# GNSS_modulis.net
KiCad netlist of a schematic drawn in Altium Designer
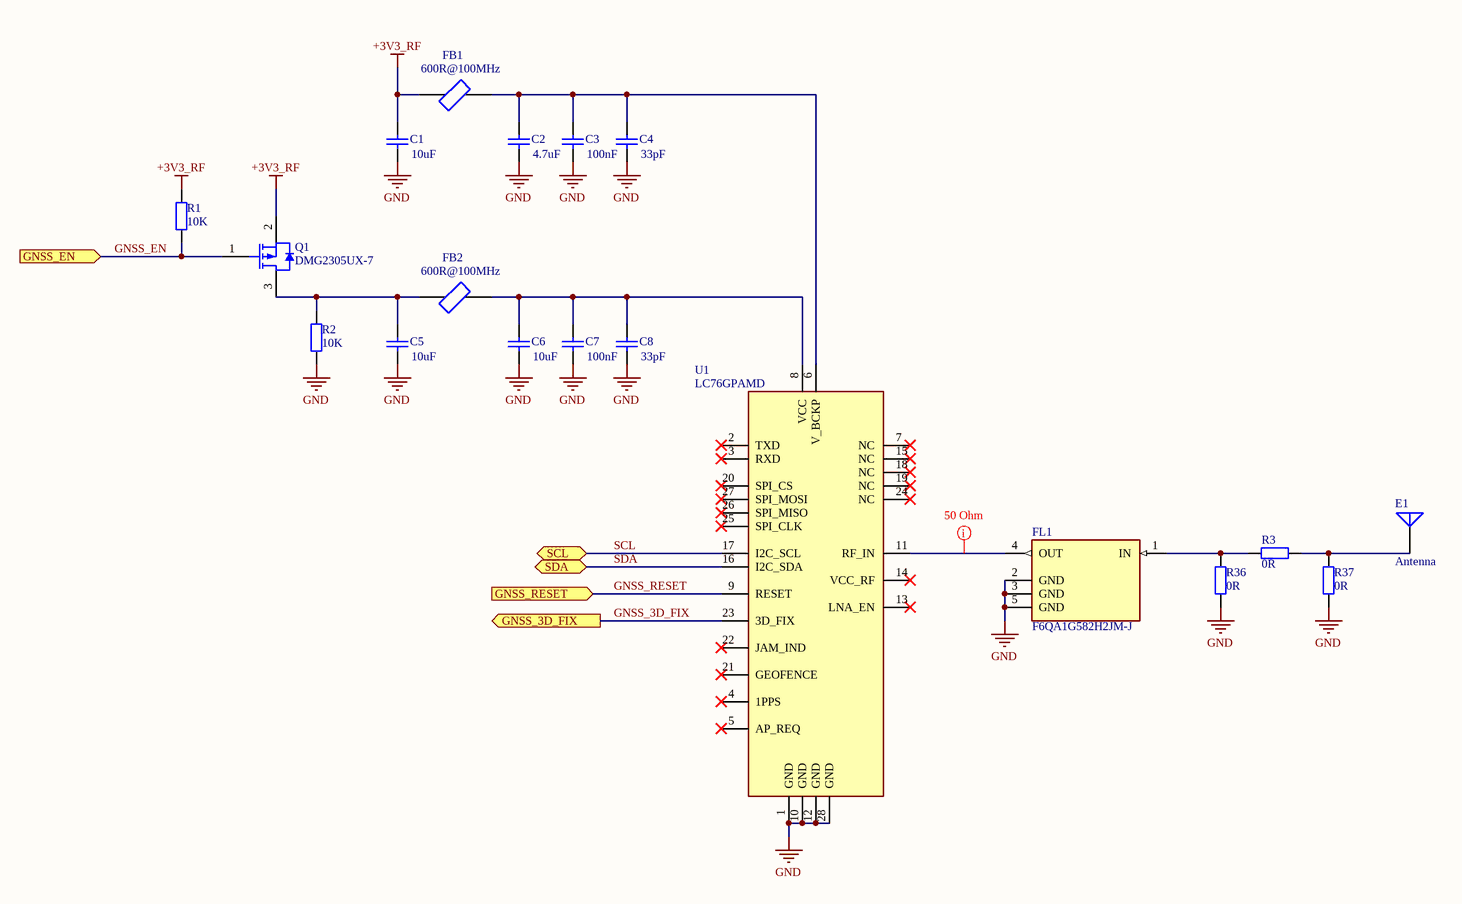
[diagram p0: GNSS modulis.SchDoc]

(export (version "E")
  (design (tool "Eeschema 10.0.6"))
  (components
    (comp (ref "C1")
      (value "10uF")
      (footprint "0402")
      (description "Capacitor")
      (fields (field (name "PUBLISHER") "Altium Limited"))
      (libsource (lib "Miscellaneous Devices") (part "Cap"))
    )
    (comp (ref "C2")
      (value "4.7uF")
      (footprint "0402")
      (description "Capacitor")
      (fields (field (name "PUBLISHER") "Altium Limited"))
      (libsource (lib "Miscellaneous Devices") (part "Cap"))
    )
    (comp (ref "C3")
      (value "100nF")
      (footprint "0402")
      (description "Capacitor")
      (fields (field (name "PUBLISHER") "Altium Limited"))
      (libsource (lib "Miscellaneous Devices") (part "Cap"))
    )
    (comp (ref "C4")
      (value "33pF")
      (footprint "0402")
      (description "Capacitor")
      (fields (field (name "PUBLISHER") "Altium Limited"))
      (libsource (lib "Miscellaneous Devices") (part "Cap"))
    )
    (comp (ref "C5")
      (value "10uF")
      (footprint "0402")
      (description "Capacitor")
      (fields (field (name "PUBLISHER") "Altium Limited"))
      (libsource (lib "Miscellaneous Devices") (part "Cap"))
    )
    (comp (ref "C6")
      (value "10uF")
      (footprint "0402")
      (description "Capacitor")
      (fields (field (name "PUBLISHER") "Altium Limited"))
      (libsource (lib "Miscellaneous Devices") (part "Cap"))
    )
    (comp (ref "C7")
      (value "100nF")
      (footprint "0402")
      (description "Capacitor")
      (fields (field (name "PUBLISHER") "Altium Limited"))
      (libsource (lib "Miscellaneous Devices") (part "Cap"))
    )
    (comp (ref "C8")
      (value "33pF")
      (footprint "0402")
      (description "Capacitor")
      (fields (field (name "PUBLISHER") "Altium Limited"))
      (libsource (lib "Miscellaneous Devices") (part "Cap"))
    )
    (comp (ref "E1")
      (value "Antenna")
      (footprint "204286-0001_MOL")
      (description "Generic Antenna")
      (fields (field (name "PUBLISHER") "Altium Limited"))
      (libsource (lib "Miscellaneous Devices") (part "Antenna"))
    )
    (comp (ref "FB1")
      (value "600R@100MHz")
      (footprint "0402 Ferrite Bead")
      (description "Ferrite Beads FERRITE BEAD 600 OHM 0603 1LN")
      (fields (field (name "MF") "Laird-Signal Integrity Products") (field (name "MP") "MI0805K400R-10"))
      (libsource (lib "Schematic_library") (part "Ferrite"))
    )
    (comp (ref "FB2")
      (value "600R@100MHz")
      (footprint "0402 Ferrite Bead")
      (description "Ferrite Beads FERRITE BEAD 600 OHM 0603 1LN")
      (fields (field (name "MF") "Laird-Signal Integrity Products") (field (name "MP") "MI0805K400R-10"))
      (libsource (lib "Schematic_library") (part "Ferrite"))
    )
    (comp (ref "FL1")
      (value "F6QA1G582H2JM-J")
      (footprint "FIL_F6QA1G582H2JM-J")
      (description "1.582GHz Frequency GPS RF SAW Filter (Surface Acoustic Wave) 1.8dB  Bandwidth 5-SMD, No Lead")
      (fields (field (name "MF") "Taiyo Yuden"))
      (libsource (lib "Schematic_library") (part "F6QA1G582H2JM-J"))
    )
    (comp (ref "Q1")
      (value "DMG2305UX-7")
      (footprint "JSCJ-SOT23-3_V")
      (description "P-Channel Plastic Encapsulate MOSFET, 12 V, 4.1 A, 3-Pin SOT23, Tape and Reel")
      (fields (field (name "MANUFACTURER") "Jiangsu Changjiang Electronics Technology"))
      (libsource (lib "Ernestas Krikščiūnas") (part "PEMOS-GSD-3"))
    )
    (comp (ref "R1")
      (value "10K")
      (footprint "SMD-0402-RES")
      (description "Resistor")
      (fields (field (name "PUBLISHER") "Altium Limited"))
      (libsource (lib "Miscellaneous Devices") (part "Res2"))
    )
    (comp (ref "R2")
      (value "10K")
      (footprint "SMD-0402-RES")
      (description "Resistor")
      (fields (field (name "PUBLISHER") "Altium Limited"))
      (libsource (lib "Miscellaneous Devices") (part "Res2"))
    )
    (comp (ref "R3")
      (value "0R")
      (footprint "SMD-0402-RES")
      (description "Resistor")
      (fields (field (name "PUBLISHER") "Altium Limited"))
      (libsource (lib "") (part "Res2_1"))
    )
    (comp (ref "R36")
      (value "0R")
      (footprint "SMD-0402-RES")
      (description "Resistor")
      (fields (field (name "PUBLISHER") "Altium Limited"))
      (libsource (lib "Miscellaneous Devices") (part "Res2"))
    )
    (comp (ref "R37")
      (value "0R")
      (footprint "SMD-0402-RES")
      (description "Resistor")
      (fields (field (name "PUBLISHER") "Altium Limited"))
      (libsource (lib "Miscellaneous Devices") (part "Res2"))
    )
    (comp (ref "U1")
      (value "LC76GPAMD")
      (footprint "SamacSys:LC76GPAMD")
      (fields (field (name "MOUSER PART NUMBER") "277-LC76GPAMD"))
      (libsource (lib "Schematic_library") (part "LC76GPAMD"))
    )
  )
  (nets
    (net (code "1") (name "+3V3_RF") (class "Default")
      (node (ref "C1") (pin "2") (pinfunction "2_2") (pintype "passive"))
      (node (ref "FB1") (pin "1") (pinfunction "1_1") (pintype "passive"))
      (node (ref "Q1") (pin "2") (pinfunction "SOURCE_2") (pintype "passive"))
      (node (ref "R1") (pin "2") (pinfunction "2_2") (pintype "passive"))
    )
    (net (code "2") (name "/GNSS_3D_FIX") (class "Default")
      (node (ref "U1") (pin "23") (pinfunction "3D_FIX_23") (pintype "passive"))
    )
    (net (code "3") (name "/GNSS_EN") (class "Default")
      (node (ref "Q1") (pin "1") (pinfunction "GATE_1") (pintype "passive"))
      (node (ref "R1") (pin "1") (pinfunction "1_1") (pintype "passive"))
    )
    (net (code "4") (name "/GNSS_RESET") (class "Default")
      (node (ref "U1") (pin "9") (pinfunction "RESET_9") (pintype "passive"))
    )
    (net (code "5") (name "/SCL") (class "Default")
      (node (ref "U1") (pin "17") (pinfunction "I2C_SCL_17") (pintype "passive"))
    )
    (net (code "6") (name "/SDA") (class "Default")
      (node (ref "U1") (pin "16") (pinfunction "I2C_SDA_16") (pintype "passive"))
    )
    (net (code "7") (name "GND") (class "Default")
      (node (ref "C1") (pin "1") (pinfunction "1_1") (pintype "passive"))
      (node (ref "C2") (pin "1") (pinfunction "1_1") (pintype "passive"))
      (node (ref "C3") (pin "1") (pinfunction "1_1") (pintype "passive"))
      (node (ref "C4") (pin "1") (pinfunction "1_1") (pintype "passive"))
      (node (ref "C5") (pin "1") (pinfunction "1_1") (pintype "passive"))
      (node (ref "C6") (pin "1") (pinfunction "1_1") (pintype "passive"))
      (node (ref "C7") (pin "1") (pinfunction "1_1") (pintype "passive"))
      (node (ref "C8") (pin "1") (pinfunction "1_1") (pintype "passive"))
      (node (ref "FL1") (pin "2") (pinfunction "GND_2") (pintype "power_in"))
      (node (ref "FL1") (pin "3") (pinfunction "GND_3") (pintype "power_in"))
      (node (ref "FL1") (pin "5") (pinfunction "GND_5") (pintype "power_in"))
      (node (ref "R2") (pin "1") (pinfunction "1_1") (pintype "passive"))
      (node (ref "R36") (pin "1") (pinfunction "1_1") (pintype "passive"))
      (node (ref "R37") (pin "1") (pinfunction "1_1") (pintype "passive"))
      (node (ref "U1") (pin "1") (pinfunction "GND_1") (pintype "passive"))
      (node (ref "U1") (pin "10") (pinfunction "GND_10") (pintype "passive"))
      (node (ref "U1") (pin "12") (pinfunction "GND_12") (pintype "passive"))
      (node (ref "U1") (pin "28") (pinfunction "GND_28") (pintype "passive"))
    )
    (net (code "8") (name "Net-(E1-A)") (class "Default")
      (node (ref "E1") (pin "1") (pinfunction "A_1") (pintype "passive"))
      (node (ref "R3") (pin "2") (pinfunction "2_2") (pintype "passive"))
      (node (ref "R37") (pin "2") (pinfunction "2_2") (pintype "passive"))
    )
    (net (code "9") (name "Net-(FL1-IN)") (class "Default")
      (node (ref "FL1") (pin "1") (pinfunction "IN_1") (pintype "input"))
      (node (ref "R3") (pin "1") (pinfunction "1_1") (pintype "passive"))
      (node (ref "R36") (pin "2") (pinfunction "2_2") (pintype "passive"))
    )
    (net (code "10") (name "Net-(FL1-OUT)") (class "Default")
      (node (ref "FL1") (pin "4") (pinfunction "OUT_4") (pintype "output"))
      (node (ref "U1") (pin "11") (pinfunction "RF_IN_11") (pintype "passive"))
    )
    (net (code "11") (name "Net-(Q1-DRAIN)") (class "Default")
      (node (ref "C5") (pin "2") (pinfunction "2_2") (pintype "passive"))
      (node (ref "FB2") (pin "1") (pinfunction "1_1") (pintype "passive"))
      (node (ref "Q1") (pin "3") (pinfunction "DRAIN_3") (pintype "passive"))
      (node (ref "R2") (pin "2") (pinfunction "2_2") (pintype "passive"))
    )
    (net (code "12") (name "Net-(U1-VCC)") (class "Default")
      (node (ref "C6") (pin "2") (pinfunction "2_2") (pintype "passive"))
      (node (ref "C7") (pin "2") (pinfunction "2_2") (pintype "passive"))
      (node (ref "C8") (pin "2") (pinfunction "2_2") (pintype "passive"))
      (node (ref "FB2") (pin "2") (pinfunction "2_2") (pintype "passive"))
      (node (ref "U1") (pin "8") (pinfunction "VCC_8") (pintype "passive"))
    )
    (net (code "13") (name "Net-(U1-V_BCKP)") (class "Default")
      (node (ref "C2") (pin "2") (pinfunction "2_2") (pintype "passive"))
      (node (ref "C3") (pin "2") (pinfunction "2_2") (pintype "passive"))
      (node (ref "C4") (pin "2") (pinfunction "2_2") (pintype "passive"))
      (node (ref "FB1") (pin "2") (pinfunction "2_2") (pintype "passive"))
      (node (ref "U1") (pin "6") (pinfunction "V_BCKP_6") (pintype "passive"))
    )
    (net (code "14") (name "unconnected-(U1-1PPS-Pad4)") (class "Default")
      (node (ref "U1") (pin "4") (pinfunction "1PPS_4") (pintype "passive+no_connect"))
    )
    (net (code "15") (name "unconnected-(U1-AP_REQ-Pad5)") (class "Default")
      (node (ref "U1") (pin "5") (pinfunction "AP_REQ_5") (pintype "passive+no_connect"))
    )
    (net (code "16") (name "unconnected-(U1-GEOFENCE-Pad21)") (class "Default")
      (node (ref "U1") (pin "21") (pinfunction "GEOFENCE_21") (pintype "passive+no_connect"))
    )
    (net (code "17") (name "unconnected-(U1-JAM_IND-Pad22)") (class "Default")
      (node (ref "U1") (pin "22") (pinfunction "JAM_IND_22") (pintype "passive+no_connect"))
    )
    (net (code "18") (name "unconnected-(U1-LNA_EN-Pad13)") (class "Default")
      (node (ref "U1") (pin "13") (pinfunction "LNA_EN_13") (pintype "passive+no_connect"))
    )
    (net (code "19") (name "unconnected-(U1-NC-Pad7)") (class "Default")
      (node (ref "U1") (pin "7") (pinfunction "NC_7") (pintype "passive+no_connect"))
    )
    (net (code "20") (name "unconnected-(U1-NC-Pad15)") (class "Default")
      (node (ref "U1") (pin "15") (pinfunction "NC_15") (pintype "passive+no_connect"))
    )
    (net (code "21") (name "unconnected-(U1-NC-Pad18)") (class "Default")
      (node (ref "U1") (pin "18") (pinfunction "NC_18") (pintype "passive+no_connect"))
    )
    (net (code "22") (name "unconnected-(U1-NC-Pad19)") (class "Default")
      (node (ref "U1") (pin "19") (pinfunction "NC_19") (pintype "passive+no_connect"))
    )
    (net (code "23") (name "unconnected-(U1-NC-Pad24)") (class "Default")
      (node (ref "U1") (pin "24") (pinfunction "NC_24") (pintype "passive+no_connect"))
    )
    (net (code "24") (name "unconnected-(U1-RXD-Pad3)") (class "Default")
      (node (ref "U1") (pin "3") (pinfunction "RXD_3") (pintype "passive+no_connect"))
    )
    (net (code "25") (name "unconnected-(U1-SPI_CLK-Pad25)") (class "Default")
      (node (ref "U1") (pin "25") (pinfunction "SPI_CLK_25") (pintype "passive+no_connect"))
    )
    (net (code "26") (name "unconnected-(U1-SPI_CS-Pad20)") (class "Default")
      (node (ref "U1") (pin "20") (pinfunction "SPI_CS_20") (pintype "passive+no_connect"))
    )
    (net (code "27") (name "unconnected-(U1-SPI_MISO-Pad26)") (class "Default")
      (node (ref "U1") (pin "26") (pinfunction "SPI_MISO_26") (pintype "passive+no_connect"))
    )
    (net (code "28") (name "unconnected-(U1-SPI_MOSI-Pad27)") (class "Default")
      (node (ref "U1") (pin "27") (pinfunction "SPI_MOSI_27") (pintype "passive+no_connect"))
    )
    (net (code "29") (name "unconnected-(U1-TXD-Pad2)") (class "Default")
      (node (ref "U1") (pin "2") (pinfunction "TXD_2") (pintype "passive+no_connect"))
    )
    (net (code "30") (name "unconnected-(U1-VCC_RF-Pad14)") (class "Default")
      (node (ref "U1") (pin "14") (pinfunction "VCC_RF_14") (pintype "passive+no_connect"))
    )
  )
)
